# HSBASIC.net
KiCad netlist of a schematic drawn in EAGLE
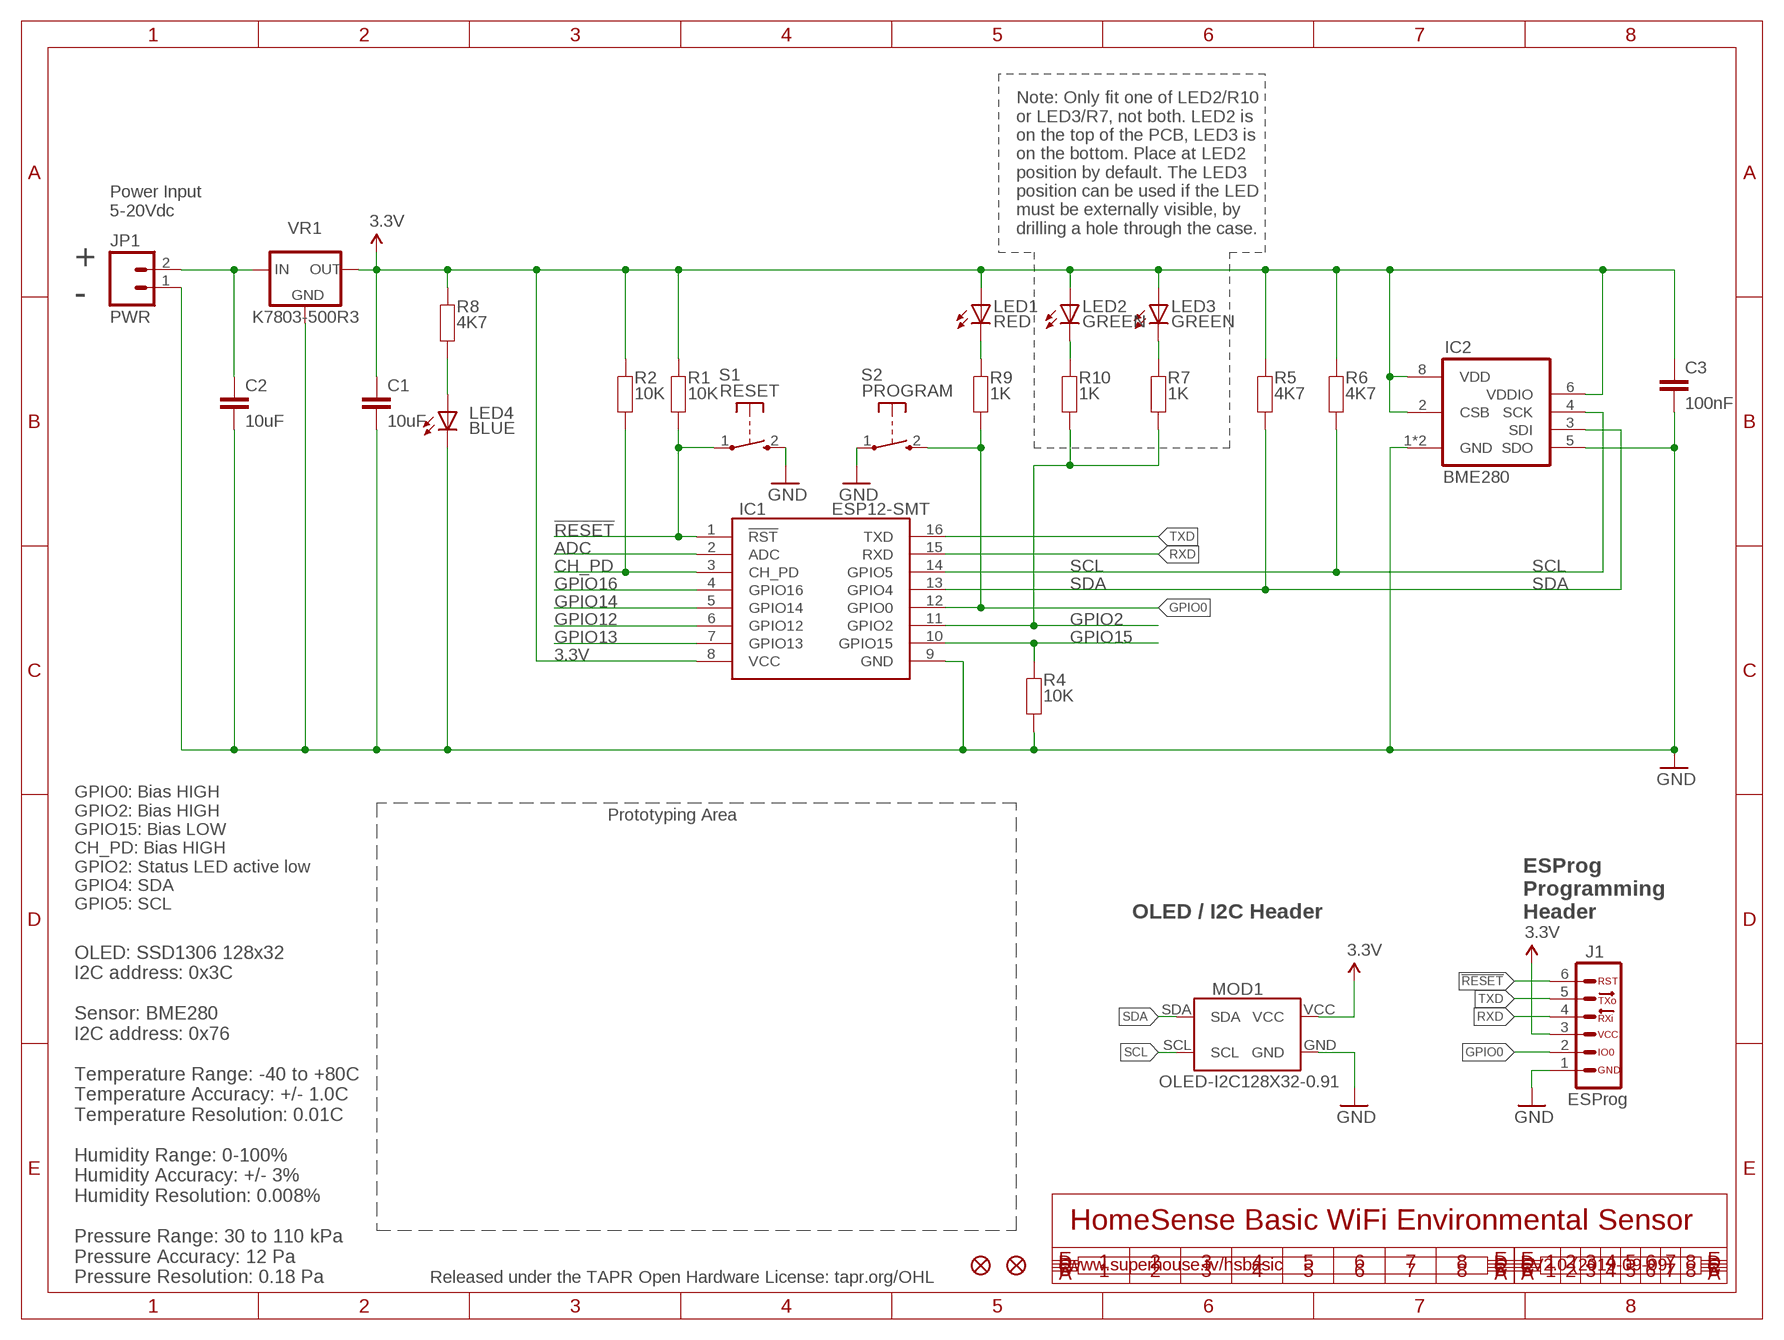
[diagram p0: schematic, sheet 1]

(export (version "E")
  (design (tool "Eeschema 10.0.6"))
  (components
    (comp (ref "C1")
      (value "10uF")
      (footprint "eagle-import:C0805")
      (libsource (lib "eagle-import") (part "CAP0805"))
    )
    (comp (ref "C2")
      (value "10uF")
      (footprint "eagle-import:C0805")
      (libsource (lib "eagle-import") (part "CAP0805"))
    )
    (comp (ref "C3")
      (value "100nF")
      (footprint "eagle-import:C0603")
      (libsource (lib "eagle-import") (part "CAP0603"))
    )
    (comp (ref "FID2")
      (value "FIDUCIAL1X2.5")
      (footprint "eagle-import:FIDUCIAL-1X2.5")
      (libsource (lib "eagle-import") (part "FIDUCIAL1X2.5"))
    )
    (comp (ref "FID3")
      (value "FIDUCIAL1X2.5")
      (footprint "eagle-import:FIDUCIAL-1X2.5")
      (libsource (lib "eagle-import") (part "FIDUCIAL1X2.5"))
    )
    (comp (ref "IC1")
      (value "ESP12-SMT")
      (footprint "eagle-import:ESP12")
      (libsource (lib "eagle-import") (part "ESP12-SMT"))
    )
    (comp (ref "IC2")
      (value "BME280")
      (footprint "eagle-import:BME280")
      (libsource (lib "eagle-import") (part "BME280"))
    )
    (comp (ref "J1")
      (value "ESPROG-SOCKET")
      (footprint "eagle-import:ESPROG-S")
      (libsource (lib "eagle-import") (part "ESPROG-SOCKET"))
    )
    (comp (ref "JP1")
      (value "PWR")
      (footprint "eagle-import:1X02")
      (libsource (lib "eagle-import") (part "M02PTH"))
    )
    (comp (ref "LED1")
      (value "RED")
      (footprint "eagle-import:LED-0603")
      (libsource (lib "eagle-import") (part "LED0603"))
    )
    (comp (ref "LED2")
      (value "GREEN")
      (footprint "eagle-import:LED-0603")
      (libsource (lib "eagle-import") (part "LED0603"))
    )
    (comp (ref "LED3")
      (value "GREEN")
      (footprint "eagle-import:LED-0603")
      (libsource (lib "eagle-import") (part "LED0603"))
    )
    (comp (ref "LED4")
      (value "BLUE")
      (footprint "eagle-import:LED-0603")
      (libsource (lib "eagle-import") (part "LED0603"))
    )
    (comp (ref "MOD1")
      (value "OLED-I2C128X32-0.91")
      (footprint "eagle-import:OLED-128X32-0.91")
      (libsource (lib "eagle-import") (part "OLED-I2C128X32-0.91"))
    )
    (comp (ref "R1")
      (value "10K")
      (footprint "eagle-import:R0603")
      (libsource (lib "eagle-import") (part "RESISTOR0603"))
    )
    (comp (ref "R2")
      (value "10K")
      (footprint "eagle-import:R0603")
      (libsource (lib "eagle-import") (part "RESISTOR0603"))
    )
    (comp (ref "R4")
      (value "10K")
      (footprint "eagle-import:R0603")
      (libsource (lib "eagle-import") (part "RESISTOR0603"))
    )
    (comp (ref "R5")
      (value "4K7")
      (footprint "eagle-import:R0603")
      (libsource (lib "eagle-import") (part "RESISTOR0603"))
    )
    (comp (ref "R6")
      (value "4K7")
      (footprint "eagle-import:R0603")
      (libsource (lib "eagle-import") (part "RESISTOR0603"))
    )
    (comp (ref "R7")
      (value "1K")
      (footprint "eagle-import:R0603")
      (libsource (lib "eagle-import") (part "RESISTOR0603"))
    )
    (comp (ref "R8")
      (value "4K7")
      (footprint "eagle-import:R0603")
      (libsource (lib "eagle-import") (part "RESISTOR0603"))
    )
    (comp (ref "R9")
      (value "1K")
      (footprint "eagle-import:R0603")
      (libsource (lib "eagle-import") (part "RESISTOR0603"))
    )
    (comp (ref "R10")
      (value "1K")
      (footprint "eagle-import:R0603")
      (libsource (lib "eagle-import") (part "RESISTOR0603"))
    )
    (comp (ref "S1")
      (value "RESET")
      (footprint "eagle-import:TACTILE_SMT_3X4X2")
      (libsource (lib "eagle-import") (part "TAC_SWITCH_2PINSMT"))
    )
    (comp (ref "S2")
      (value "PROGRAM")
      (footprint "eagle-import:TACTILE_SMT_3X4X2")
      (libsource (lib "eagle-import") (part "TAC_SWITCH_2PINSMT"))
    )
    (comp (ref "VR1")
      (value "K7803-500R3")
      (footprint "eagle-import:K78XX-500R3-FLAT")
      (libsource (lib "eagle-import") (part "K78XX-500R3-FLAT"))
    )
  )
  (nets
    (net (code "1") (name "/ADC") (class "Default")
      (node (ref "IC1") (pin "2") (pinfunction "ADC_2") (pintype "input"))
    )
    (net (code "2") (name "/CH_PD") (class "Default")
      (node (ref "IC1") (pin "3") (pinfunction "CH_PD_3") (pintype "input"))
      (node (ref "R2") (pin "1") (pinfunction "1_1") (pintype "passive"))
    )
    (net (code "3") (name "/GPIO2") (class "Default")
      (node (ref "IC1") (pin "11") (pinfunction "GPIO2_11") (pintype "bidirectional"))
      (node (ref "R10") (pin "1") (pinfunction "1_1") (pintype "passive"))
      (node (ref "R7") (pin "1") (pinfunction "1_1") (pintype "passive"))
    )
    (net (code "4") (name "/GPIO12") (class "Default")
      (node (ref "IC1") (pin "6") (pinfunction "GPIO12_6") (pintype "bidirectional"))
    )
    (net (code "5") (name "/GPIO13") (class "Default")
      (node (ref "IC1") (pin "7") (pinfunction "GPIO13_7") (pintype "bidirectional"))
    )
    (net (code "6") (name "/GPIO14") (class "Default")
      (node (ref "IC1") (pin "5") (pinfunction "GPIO14_5") (pintype "bidirectional"))
    )
    (net (code "7") (name "/GPIO15") (class "Default")
      (node (ref "IC1") (pin "10") (pinfunction "GPIO15_10") (pintype "bidirectional"))
      (node (ref "R4") (pin "2") (pinfunction "2_2") (pintype "passive"))
    )
    (net (code "8") (name "/GPIO16") (class "Default")
      (node (ref "IC1") (pin "4") (pinfunction "GPIO16_4") (pintype "bidirectional"))
    )
    (net (code "9") (name "/~{RESET}") (class "Default")
      (node (ref "IC1") (pin "1") (pinfunction "~{RST}_1") (pintype "bidirectional"))
      (node (ref "J1") (pin "6") (pinfunction "6_6") (pintype "passive"))
      (node (ref "R1") (pin "1") (pinfunction "1_1") (pintype "passive"))
      (node (ref "S1") (pin "1") (pinfunction "P_1") (pintype "passive"))
    )
    (net (code "10") (name "3.3V") (class "Default")
      (node (ref "C1") (pin "1") (pinfunction "1_1") (pintype "passive"))
      (node (ref "C3") (pin "1") (pinfunction "1_1") (pintype "passive"))
      (node (ref "IC1") (pin "8") (pinfunction "VCC_8") (pintype "power_in"))
      (node (ref "IC2") (pin "2") (pinfunction "CSB_2") (pintype "input"))
      (node (ref "IC2") (pin "6") (pinfunction "VDDIO_6") (pintype "power_in"))
      (node (ref "IC2") (pin "8") (pinfunction "VDD_8") (pintype "power_in"))
      (node (ref "J1") (pin "3") (pinfunction "3_3") (pintype "passive"))
      (node (ref "LED1") (pin "A") (pinfunction "A_A") (pintype "passive"))
      (node (ref "LED2") (pin "A") (pinfunction "A_A") (pintype "passive"))
      (node (ref "LED3") (pin "A") (pinfunction "A_A") (pintype "passive"))
      (node (ref "MOD1") (pin "VCC") (pinfunction "VCC_VCC") (pintype "bidirectional"))
      (node (ref "R1") (pin "2") (pinfunction "2_2") (pintype "passive"))
      (node (ref "R2") (pin "2") (pinfunction "2_2") (pintype "passive"))
      (node (ref "R5") (pin "2") (pinfunction "2_2") (pintype "passive"))
      (node (ref "R6") (pin "2") (pinfunction "2_2") (pintype "passive"))
      (node (ref "R8") (pin "2") (pinfunction "2_2") (pintype "passive"))
      (node (ref "VR1") (pin "3") (pinfunction "OUT_3") (pintype "output"))
    )
    (net (code "11") (name "GND") (class "Default")
      (node (ref "C1") (pin "2") (pinfunction "2_2") (pintype "passive"))
      (node (ref "C2") (pin "2") (pinfunction "2_2") (pintype "passive"))
      (node (ref "C3") (pin "2") (pinfunction "2_2") (pintype "passive"))
      (node (ref "IC1") (pin "9") (pinfunction "GND_9") (pintype "power_in"))
      (node (ref "IC2") (pin "1") (pinfunction "GND_1") (pintype "power_in"))
      (node (ref "IC2") (pin "5") (pinfunction "SDO_5") (pintype "input"))
      (node (ref "IC2") (pin "7") (pinfunction "GND_7") (pintype "power_in"))
      (node (ref "J1") (pin "1") (pinfunction "1_1") (pintype "passive"))
      (node (ref "JP1") (pin "1") (pinfunction "1_1") (pintype "passive"))
      (node (ref "LED4") (pin "C") (pinfunction "C_C") (pintype "passive"))
      (node (ref "MOD1") (pin "GND") (pinfunction "GND_GND") (pintype "bidirectional"))
      (node (ref "R4") (pin "1") (pinfunction "1_1") (pintype "passive"))
      (node (ref "S1") (pin "2") (pinfunction "S_2") (pintype "passive"))
      (node (ref "S2") (pin "1") (pinfunction "P_1") (pintype "passive"))
      (node (ref "VR1") (pin "2") (pinfunction "GND_2") (pintype "input"))
    )
    (net (code "12") (name "GPIO0") (class "Default")
      (node (ref "IC1") (pin "12") (pinfunction "GPIO0_12") (pintype "bidirectional"))
      (node (ref "J1") (pin "2") (pinfunction "2_2") (pintype "passive"))
      (node (ref "R9") (pin "1") (pinfunction "1_1") (pintype "passive"))
      (node (ref "S2") (pin "2") (pinfunction "S_2") (pintype "passive"))
    )
    (net (code "13") (name "Net-(LED1-PadC)") (class "Default")
      (node (ref "LED1") (pin "C") (pinfunction "C_C") (pintype "passive"))
      (node (ref "R9") (pin "2") (pinfunction "2_2") (pintype "passive"))
    )
    (net (code "14") (name "Net-(LED2-PadC)") (class "Default")
      (node (ref "LED2") (pin "C") (pinfunction "C_C") (pintype "passive"))
      (node (ref "R10") (pin "2") (pinfunction "2_2") (pintype "passive"))
    )
    (net (code "15") (name "Net-(LED3-PadC)") (class "Default")
      (node (ref "LED3") (pin "C") (pinfunction "C_C") (pintype "passive"))
      (node (ref "R7") (pin "2") (pinfunction "2_2") (pintype "passive"))
    )
    (net (code "16") (name "Net-(LED4-PadA)") (class "Default")
      (node (ref "LED4") (pin "A") (pinfunction "A_A") (pintype "passive"))
      (node (ref "R8") (pin "1") (pinfunction "1_1") (pintype "passive"))
    )
    (net (code "17") (name "Net-(VR1-IN)") (class "Default")
      (node (ref "C2") (pin "1") (pinfunction "1_1") (pintype "passive"))
      (node (ref "JP1") (pin "2") (pinfunction "2_2") (pintype "passive"))
      (node (ref "VR1") (pin "1") (pinfunction "IN_1") (pintype "input"))
    )
    (net (code "18") (name "RXD") (class "Default")
      (node (ref "IC1") (pin "15") (pinfunction "RXD_15") (pintype "input"))
      (node (ref "J1") (pin "4") (pinfunction "4_4") (pintype "passive"))
    )
    (net (code "19") (name "SCL") (class "Default")
      (node (ref "IC1") (pin "14") (pinfunction "GPIO5_14") (pintype "bidirectional"))
      (node (ref "IC2") (pin "4") (pinfunction "SCK_4") (pintype "bidirectional"))
      (node (ref "MOD1") (pin "SCL") (pinfunction "SCL_SCL") (pintype "bidirectional"))
      (node (ref "R6") (pin "1") (pinfunction "1_1") (pintype "passive"))
    )
    (net (code "20") (name "SDA") (class "Default")
      (node (ref "IC1") (pin "13") (pinfunction "GPIO4_13") (pintype "bidirectional"))
      (node (ref "IC2") (pin "3") (pinfunction "SDI_3") (pintype "bidirectional"))
      (node (ref "MOD1") (pin "SDA") (pinfunction "SDA_SDA") (pintype "bidirectional"))
      (node (ref "R5") (pin "1") (pinfunction "1_1") (pintype "passive"))
    )
    (net (code "21") (name "TXD") (class "Default")
      (node (ref "IC1") (pin "16") (pinfunction "TXD_16") (pintype "output"))
      (node (ref "J1") (pin "5") (pinfunction "5_5") (pintype "passive"))
    )
  )
)
